# APP_1_DAC_m.net
KiCad netlist of a schematic drawn in Altium Designer
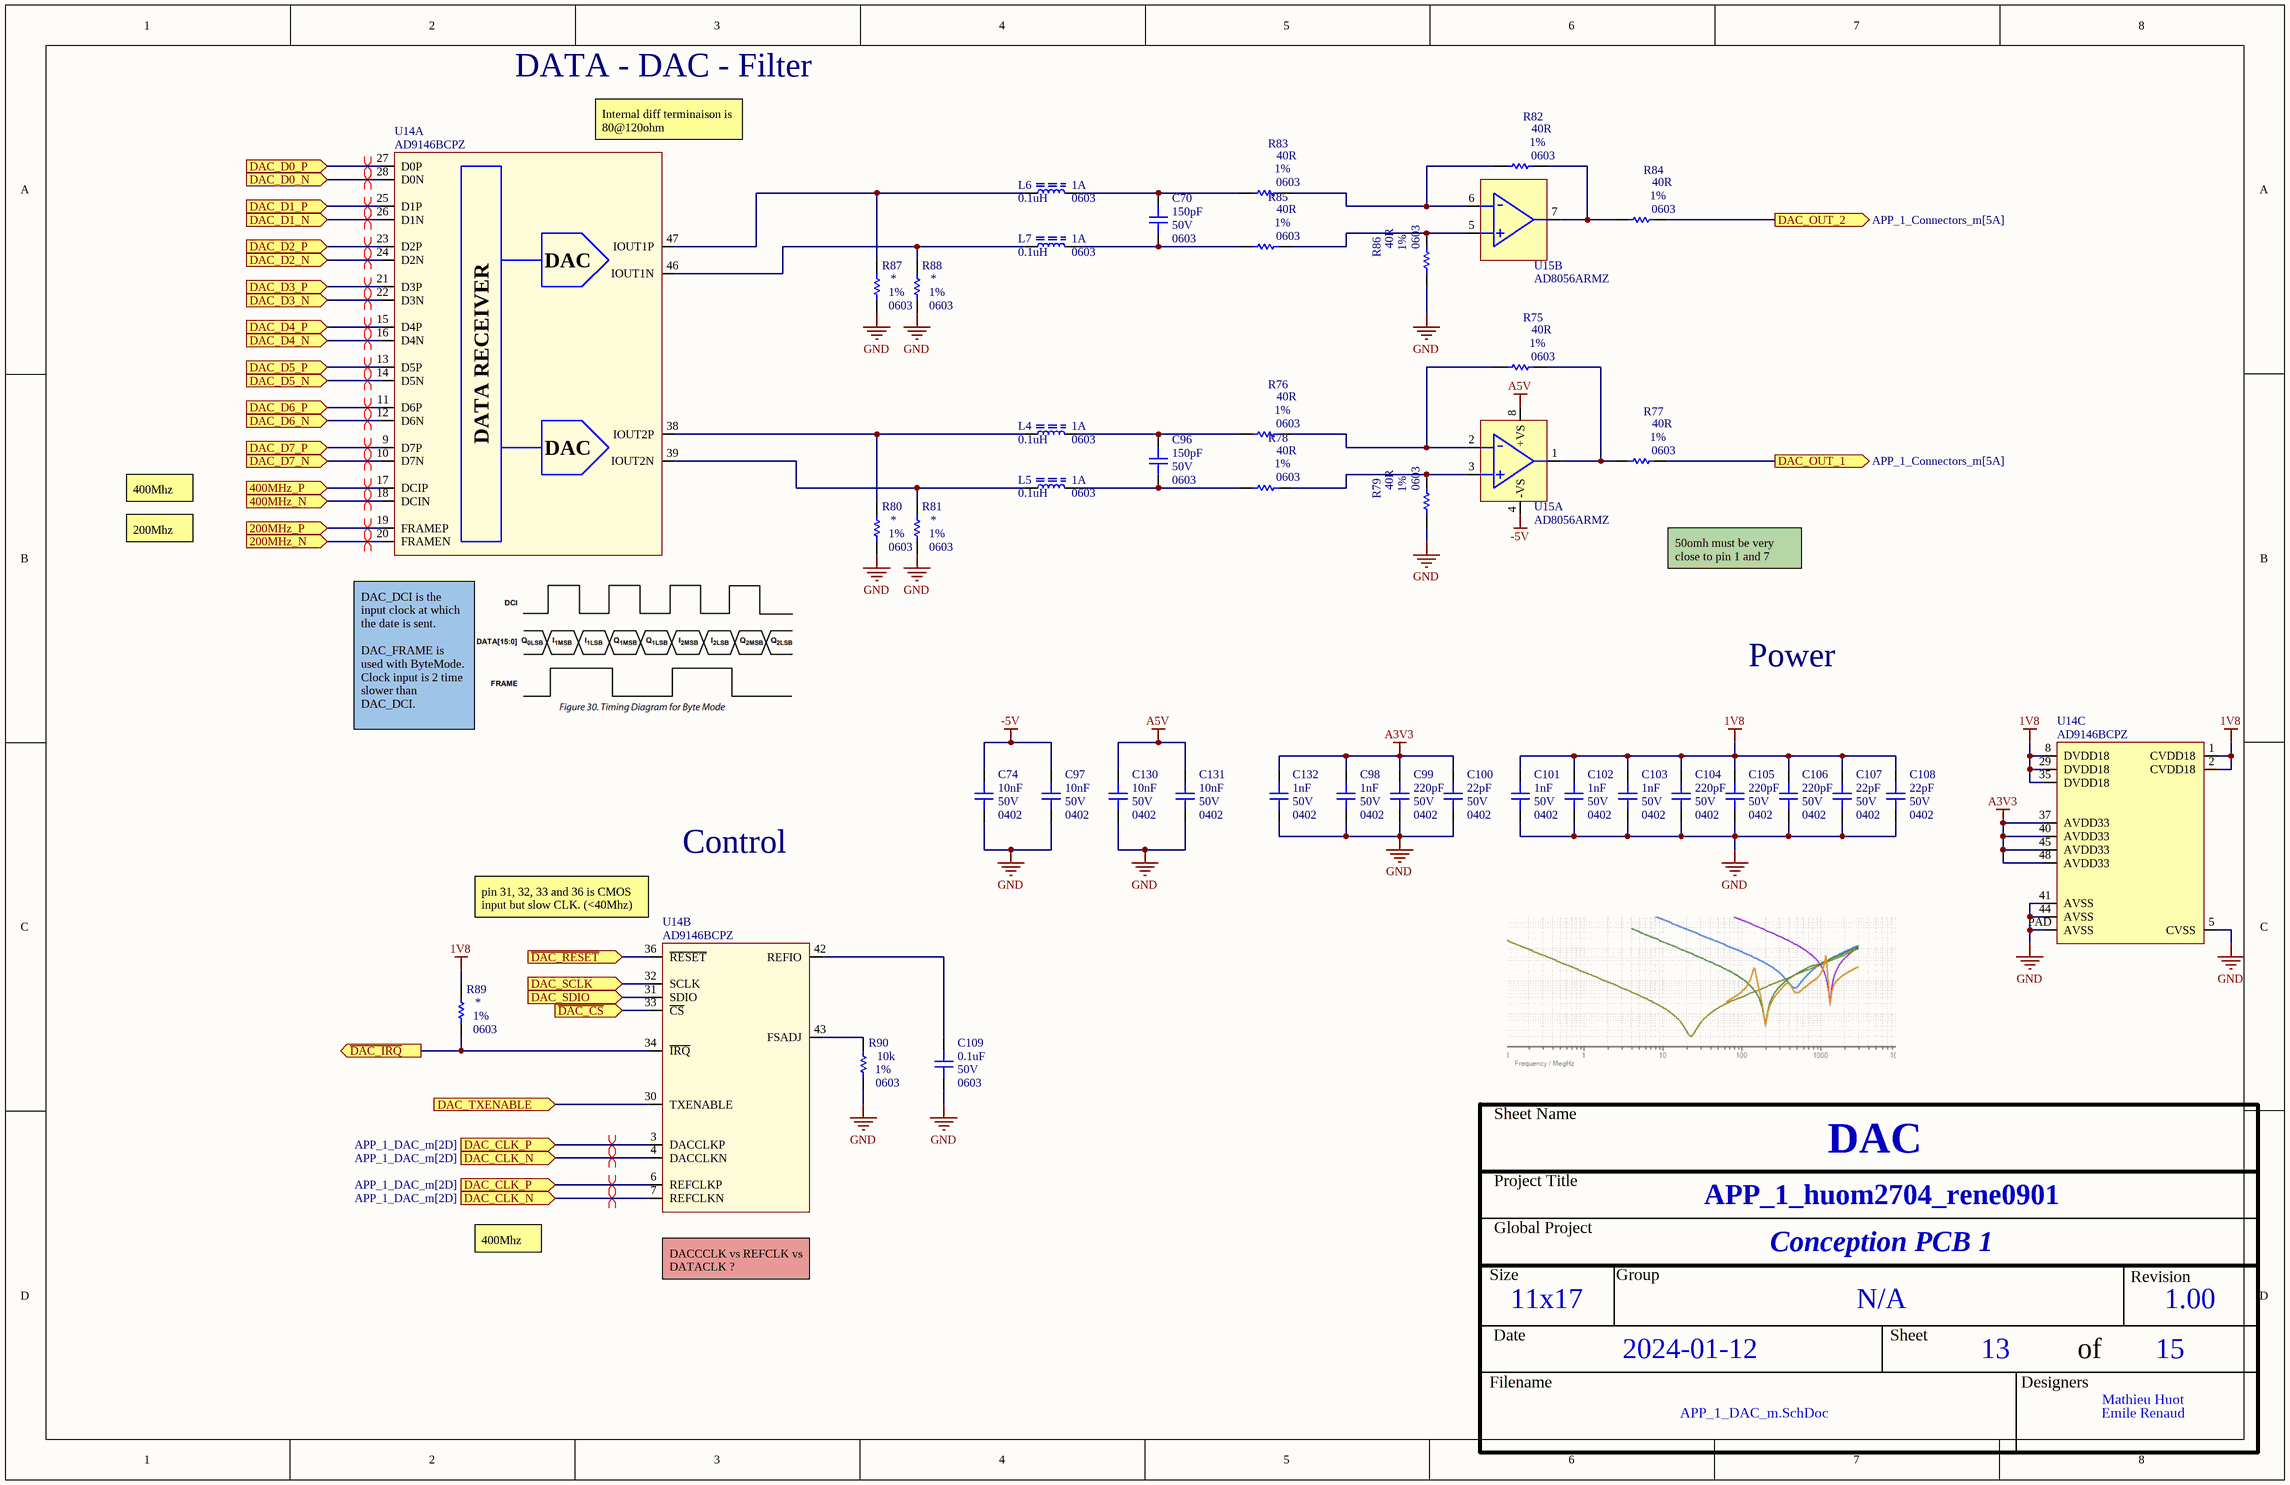
[diagram p0: APP_1_DAC_m.SchDoc]

(export (version "E")
  (design (tool "Eeschema 10.0.6"))
  (components
    (comp (ref "C70")
      (value "150pF")
      (footprint "CAP_0603")
      (description "CAP - 0603")
      (fields
        (field (name "VOLTAGE") "50V")
        (field (name "PACKAGE") "0603")
        (field (name "CREATEDBY") "Jonathan Bouchard")
      )
      (libsource (lib "S7CAS_LIB2023") (part "CAP - 0603"))
    )
    (comp (ref "C74")
      (value "10nF")
      (footprint "CAP_0402")
      (description "CAP - 0402")
      (fields
        (field (name "VOLTAGE") "50V")
        (field (name "PACKAGE") "0402")
        (field (name "CREATEDBY") "Jonathan Bouchard")
      )
      (libsource (lib "S7CAS_LIB2023") (part "CAP - 0402"))
    )
    (comp (ref "C96")
      (value "150pF")
      (footprint "CAP_0603")
      (description "CAP - 0603")
      (fields
        (field (name "VOLTAGE") "50V")
        (field (name "PACKAGE") "0603")
        (field (name "CREATEDBY") "Jonathan Bouchard")
      )
      (libsource (lib "S7CAS_LIB2023") (part "CAP - 0603"))
    )
    (comp (ref "C97")
      (value "10nF")
      (footprint "CAP_0402")
      (description "CAP - 0402")
      (fields
        (field (name "VOLTAGE") "50V")
        (field (name "PACKAGE") "0402")
        (field (name "CREATEDBY") "Jonathan Bouchard")
      )
      (libsource (lib "S7CAS_LIB2023") (part "CAP - 0402"))
    )
    (comp (ref "C98")
      (value "1nF")
      (footprint "CAP_0402")
      (description "CAP - 0402")
      (fields
        (field (name "VOLTAGE") "50V")
        (field (name "PACKAGE") "0402")
        (field (name "CREATEDBY") "Jonathan Bouchard")
      )
      (libsource (lib "S7CAS_LIB2023") (part "CAP - 0402"))
    )
    (comp (ref "C99")
      (value "220pF")
      (footprint "CAP_0402")
      (description "CAP - 0402")
      (fields
        (field (name "VOLTAGE") "50V")
        (field (name "PACKAGE") "0402")
        (field (name "CREATEDBY") "Jonathan Bouchard")
      )
      (libsource (lib "S7CAS_LIB2023") (part "CAP - 0402"))
    )
    (comp (ref "C100")
      (value "22pF")
      (footprint "CAP_0402")
      (description "CAP - 0402")
      (fields
        (field (name "VOLTAGE") "50V")
        (field (name "PACKAGE") "0402")
        (field (name "CREATEDBY") "Jonathan Bouchard")
      )
      (libsource (lib "S7CAS_LIB2023") (part "CAP - 0402"))
    )
    (comp (ref "C101")
      (value "1nF")
      (footprint "CAP_0402")
      (description "CAP - 0402")
      (fields
        (field (name "VOLTAGE") "50V")
        (field (name "PACKAGE") "0402")
        (field (name "CREATEDBY") "Jonathan Bouchard")
      )
      (libsource (lib "S7CAS_LIB2023") (part "CAP - 0402"))
    )
    (comp (ref "C102")
      (value "1nF")
      (footprint "CAP_0402")
      (description "CAP - 0402")
      (fields
        (field (name "VOLTAGE") "50V")
        (field (name "PACKAGE") "0402")
        (field (name "CREATEDBY") "Jonathan Bouchard")
      )
      (libsource (lib "S7CAS_LIB2023") (part "CAP - 0402"))
    )
    (comp (ref "C103")
      (value "1nF")
      (footprint "CAP_0402")
      (description "CAP - 0402")
      (fields
        (field (name "VOLTAGE") "50V")
        (field (name "PACKAGE") "0402")
        (field (name "CREATEDBY") "Jonathan Bouchard")
      )
      (libsource (lib "S7CAS_LIB2023") (part "CAP - 0402"))
    )
    (comp (ref "C104")
      (value "220pF")
      (footprint "CAP_0402")
      (description "CAP - 0402")
      (fields
        (field (name "VOLTAGE") "50V")
        (field (name "PACKAGE") "0402")
        (field (name "CREATEDBY") "Jonathan Bouchard")
      )
      (libsource (lib "S7CAS_LIB2023") (part "CAP - 0402"))
    )
    (comp (ref "C105")
      (value "220pF")
      (footprint "CAP_0402")
      (description "CAP - 0402")
      (fields
        (field (name "VOLTAGE") "50V")
        (field (name "PACKAGE") "0402")
        (field (name "CREATEDBY") "Jonathan Bouchard")
      )
      (libsource (lib "S7CAS_LIB2023") (part "CAP - 0402"))
    )
    (comp (ref "C106")
      (value "220pF")
      (footprint "CAP_0402")
      (description "CAP - 0402")
      (fields
        (field (name "VOLTAGE") "50V")
        (field (name "PACKAGE") "0402")
        (field (name "CREATEDBY") "Jonathan Bouchard")
      )
      (libsource (lib "S7CAS_LIB2023") (part "CAP - 0402"))
    )
    (comp (ref "C107")
      (value "22pF")
      (footprint "CAP_0402")
      (description "CAP - 0402")
      (fields
        (field (name "VOLTAGE") "50V")
        (field (name "PACKAGE") "0402")
        (field (name "CREATEDBY") "Jonathan Bouchard")
      )
      (libsource (lib "S7CAS_LIB2023") (part "CAP - 0402"))
    )
    (comp (ref "C108")
      (value "22pF")
      (footprint "CAP_0402")
      (description "CAP - 0402")
      (fields
        (field (name "VOLTAGE") "50V")
        (field (name "PACKAGE") "0402")
        (field (name "CREATEDBY") "Jonathan Bouchard")
      )
      (libsource (lib "S7CAS_LIB2023") (part "CAP - 0402"))
    )
    (comp (ref "C109")
      (value "0.1uF")
      (footprint "CAP_0603")
      (description "CAP - 0603")
      (fields
        (field (name "VOLTAGE") "50V")
        (field (name "PACKAGE") "0603")
        (field (name "CREATEDBY") "Jonathan Bouchard")
      )
      (libsource (lib "S7CAS_LIB2023") (part "CAP - 0603"))
    )
    (comp (ref "C130")
      (value "10nF")
      (footprint "CAP_0402")
      (description "CAP - 0402")
      (fields
        (field (name "VOLTAGE") "50V")
        (field (name "PACKAGE") "0402")
        (field (name "CREATEDBY") "Jonathan Bouchard")
      )
      (libsource (lib "S7CAS_LIB2023") (part "CAP - 0402"))
    )
    (comp (ref "C131")
      (value "10nF")
      (footprint "CAP_0402")
      (description "CAP - 0402")
      (fields
        (field (name "VOLTAGE") "50V")
        (field (name "PACKAGE") "0402")
        (field (name "CREATEDBY") "Jonathan Bouchard")
      )
      (libsource (lib "S7CAS_LIB2023") (part "CAP - 0402"))
    )
    (comp (ref "C132")
      (value "1nF")
      (footprint "CAP_0402")
      (description "CAP - 0402")
      (fields
        (field (name "VOLTAGE") "50V")
        (field (name "PACKAGE") "0402")
        (field (name "CREATEDBY") "Jonathan Bouchard")
      )
      (libsource (lib "S7CAS_LIB2023") (part "CAP - 0402"))
    )
    (comp (ref "L4")
      (value "0.1uH")
      (footprint "FER_0603")
      (description "FER - 0603")
      (fields
        (field (name "CURRENT") "1A")
        (field (name "PACKAGE") "0603")
        (field (name "CREATEDBY") "Jonathan Bouchard")
      )
      (libsource (lib "S7CAS_LIB2023") (part "FER - 0603"))
    )
    (comp (ref "L5")
      (value "0.1uH")
      (footprint "FER_0603")
      (description "FER - 0603")
      (fields
        (field (name "CURRENT") "1A")
        (field (name "PACKAGE") "0603")
        (field (name "CREATEDBY") "Jonathan Bouchard")
      )
      (libsource (lib "S7CAS_LIB2023") (part "FER - 0603"))
    )
    (comp (ref "L6")
      (value "0.1uH")
      (footprint "FER_0603")
      (description "FER - 0603")
      (fields
        (field (name "CURRENT") "1A")
        (field (name "PACKAGE") "0603")
        (field (name "CREATEDBY") "Jonathan Bouchard")
      )
      (libsource (lib "S7CAS_LIB2023") (part "FER - 0603"))
    )
    (comp (ref "L7")
      (value "0.1uH")
      (footprint "FER_0603")
      (description "FER - 0603")
      (fields
        (field (name "CURRENT") "1A")
        (field (name "PACKAGE") "0603")
        (field (name "CREATEDBY") "Jonathan Bouchard")
      )
      (libsource (lib "S7CAS_LIB2023") (part "FER - 0603"))
    )
    (comp (ref "R75")
      (value "40R")
      (footprint "RES_0603")
      (description "RES - 0603")
      (fields
        (field (name "PACKAGE") "0603")
        (field (name "PRECISION") "1%")
        (field (name "CREATEDBY") "Jonathan Bouchard")
      )
      (libsource (lib "S7CAS_LIB2023") (part "RES - 0603"))
    )
    (comp (ref "R76")
      (value "40R")
      (footprint "RES_0603")
      (description "RES - 0603")
      (fields
        (field (name "PACKAGE") "0603")
        (field (name "PRECISION") "1%")
        (field (name "CREATEDBY") "Jonathan Bouchard")
      )
      (libsource (lib "S7CAS_LIB2023") (part "RES - 0603"))
    )
    (comp (ref "R77")
      (value "40R")
      (footprint "RES_0603")
      (description "RES - 0603")
      (fields
        (field (name "PACKAGE") "0603")
        (field (name "PRECISION") "1%")
        (field (name "CREATEDBY") "Jonathan Bouchard")
      )
      (libsource (lib "S7CAS_LIB2023") (part "RES - 0603"))
    )
    (comp (ref "R78")
      (value "40R")
      (footprint "RES_0603")
      (description "RES - 0603")
      (fields
        (field (name "PACKAGE") "0603")
        (field (name "PRECISION") "1%")
        (field (name "CREATEDBY") "Jonathan Bouchard")
      )
      (libsource (lib "S7CAS_LIB2023") (part "RES - 0603"))
    )
    (comp (ref "R79")
      (value "40R")
      (footprint "RES_0603")
      (description "RES - 0603")
      (fields
        (field (name "PACKAGE") "0603")
        (field (name "PRECISION") "1%")
        (field (name "CREATEDBY") "Jonathan Bouchard")
      )
      (libsource (lib "S7CAS_LIB2023") (part "RES - 0603"))
    )
    (comp (ref "R80")
      (value "RES - 0603")
      (footprint "RES_0603")
      (fields
        (field (name "PACKAGE") "0603")
        (field (name "PRECISION") "1%")
        (field (name "ALTIUM_VALUE") "*")
        (field (name "CREATEDBY") "Jonathan Bouchard")
      )
      (libsource (lib "S7CAS_LIB2023") (part "RES - 0603"))
    )
    (comp (ref "R81")
      (value "RES - 0603")
      (footprint "RES_0603")
      (fields
        (field (name "PACKAGE") "0603")
        (field (name "PRECISION") "1%")
        (field (name "ALTIUM_VALUE") "*")
        (field (name "CREATEDBY") "Jonathan Bouchard")
      )
      (libsource (lib "S7CAS_LIB2023") (part "RES - 0603"))
    )
    (comp (ref "R82")
      (value "40R")
      (footprint "RES_0603")
      (description "RES - 0603")
      (fields
        (field (name "PACKAGE") "0603")
        (field (name "PRECISION") "1%")
        (field (name "CREATEDBY") "Jonathan Bouchard")
      )
      (libsource (lib "S7CAS_LIB2023") (part "RES - 0603"))
    )
    (comp (ref "R83")
      (value "40R")
      (footprint "RES_0603")
      (description "RES - 0603")
      (fields
        (field (name "PACKAGE") "0603")
        (field (name "PRECISION") "1%")
        (field (name "CREATEDBY") "Jonathan Bouchard")
      )
      (libsource (lib "S7CAS_LIB2023") (part "RES - 0603"))
    )
    (comp (ref "R84")
      (value "40R")
      (footprint "RES_0603")
      (description "RES - 0603")
      (fields
        (field (name "PACKAGE") "0603")
        (field (name "PRECISION") "1%")
        (field (name "CREATEDBY") "Jonathan Bouchard")
      )
      (libsource (lib "S7CAS_LIB2023") (part "RES - 0603"))
    )
    (comp (ref "R85")
      (value "40R")
      (footprint "RES_0603")
      (description "RES - 0603")
      (fields
        (field (name "PACKAGE") "0603")
        (field (name "PRECISION") "1%")
        (field (name "CREATEDBY") "Jonathan Bouchard")
      )
      (libsource (lib "S7CAS_LIB2023") (part "RES - 0603"))
    )
    (comp (ref "R86")
      (value "40R")
      (footprint "RES_0603")
      (description "RES - 0603")
      (fields
        (field (name "PACKAGE") "0603")
        (field (name "PRECISION") "1%")
        (field (name "CREATEDBY") "Jonathan Bouchard")
      )
      (libsource (lib "S7CAS_LIB2023") (part "RES - 0603"))
    )
    (comp (ref "R87")
      (value "RES - 0603")
      (footprint "RES_0603")
      (fields
        (field (name "PACKAGE") "0603")
        (field (name "PRECISION") "1%")
        (field (name "ALTIUM_VALUE") "*")
        (field (name "CREATEDBY") "Jonathan Bouchard")
      )
      (libsource (lib "S7CAS_LIB2023") (part "RES - 0603"))
    )
    (comp (ref "R88")
      (value "RES - 0603")
      (footprint "RES_0603")
      (fields
        (field (name "PACKAGE") "0603")
        (field (name "PRECISION") "1%")
        (field (name "ALTIUM_VALUE") "*")
        (field (name "CREATEDBY") "Jonathan Bouchard")
      )
      (libsource (lib "S7CAS_LIB2023") (part "RES - 0603"))
    )
    (comp (ref "R89")
      (value "RES - 0603")
      (footprint "RES_0603")
      (fields
        (field (name "PACKAGE") "0603")
        (field (name "PRECISION") "1%")
        (field (name "ALTIUM_VALUE") "*")
        (field (name "CREATEDBY") "Jonathan Bouchard")
      )
      (libsource (lib "S7CAS_LIB2023") (part "RES - 0603"))
    )
    (comp (ref "R90")
      (value "10k")
      (footprint "RES_0603")
      (description "RES - 0603")
      (fields
        (field (name "PACKAGE") "0603")
        (field (name "PRECISION") "1%")
        (field (name "CREATEDBY") "Jonathan Bouchard")
      )
      (libsource (lib "S7CAS_LIB2023") (part "RES - 0603"))
    )
    (comp (ref "U14")
      (value "AD9146BCPZ")
      (footprint "DAC_AD9146BCPZ")
      (description "DAC - 16BIT SRL HIGH SPEED - QFN-48")
      (fields
        (field (name "VOLTAGE") "3.13 V ~ 3.47 V / 1.71 V ~ 1.89 V")
        (field (name "MFG") "Analog Devices Inc.")
        (field (name "CREATEDBY") "Jonathan Bouchard")
      )
      (libsource (lib "S7CAS_LIB2023") (part "DAC_AD9146BCPZ"))
    )
    (comp (ref "U15")
      (value "AD8056ARMZ")
      (footprint "OPAMP_AD8056ARMZ")
      (description "OPAMP - VFB 300MHZ - 8MSOP")
      (fields
        (field (name "VOLTAGE") "8 V ~ 12 V, ±4 V ~ 6 V")
        (field (name "MFG") "Analog Devices")
        (field (name "CREATEDBY") "Jonathan Bouchard")
      )
      (libsource (lib "S7CAS_LIB2023") (part "OPAMP_AD8056ARMZ"))
    )
  )
  (nets
    (net (code "1") (name "-5V") (class "Default")
      (node (ref "C74") (pin "2") (pinfunction "2_2") (pintype "passive"))
      (node (ref "C97") (pin "2") (pinfunction "2_2") (pintype "passive"))
      (node (ref "U15") (pin "4") (pinfunction "-VS_4") (pintype "passive"))
    )
    (net (code "2") (name "/200MHz_N") (class "Default")
      (node (ref "U14") (pin "20") (pinfunction "FRAMEN_20") (pintype "passive"))
    )
    (net (code "3") (name "/200MHz_P") (class "Default")
      (node (ref "U14") (pin "19") (pinfunction "FRAMEP_19") (pintype "passive"))
    )
    (net (code "4") (name "/400MHz_N") (class "Default")
      (node (ref "U14") (pin "18") (pinfunction "DCIN_18") (pintype "passive"))
    )
    (net (code "5") (name "/400MHz_P") (class "Default")
      (node (ref "U14") (pin "17") (pinfunction "DCIP_17") (pintype "passive"))
    )
    (net (code "6") (name "/DAC_CLK_N") (class "Default")
      (node (ref "U14") (pin "4") (pinfunction "DACCLKN_4") (pintype "passive"))
      (node (ref "U14") (pin "7") (pinfunction "REFCLKN_7") (pintype "passive"))
    )
    (net (code "7") (name "/DAC_CLK_P") (class "Default")
      (node (ref "U14") (pin "3") (pinfunction "DACCLKP_3") (pintype "passive"))
      (node (ref "U14") (pin "6") (pinfunction "REFCLKP_6") (pintype "passive"))
    )
    (net (code "8") (name "/DAC_D0_N") (class "Default")
      (node (ref "U14") (pin "28") (pinfunction "D0N_28") (pintype "passive"))
    )
    (net (code "9") (name "/DAC_D0_P") (class "Default")
      (node (ref "U14") (pin "27") (pinfunction "D0P_27") (pintype "passive"))
    )
    (net (code "10") (name "/DAC_D1_N") (class "Default")
      (node (ref "U14") (pin "26") (pinfunction "D1N_26") (pintype "passive"))
    )
    (net (code "11") (name "/DAC_D1_P") (class "Default")
      (node (ref "U14") (pin "25") (pinfunction "D1P_25") (pintype "passive"))
    )
    (net (code "12") (name "/DAC_D2_N") (class "Default")
      (node (ref "U14") (pin "24") (pinfunction "D2N_24") (pintype "passive"))
    )
    (net (code "13") (name "/DAC_D2_P") (class "Default")
      (node (ref "U14") (pin "23") (pinfunction "D2P_23") (pintype "passive"))
    )
    (net (code "14") (name "/DAC_D3_N") (class "Default")
      (node (ref "U14") (pin "22") (pinfunction "D3N_22") (pintype "passive"))
    )
    (net (code "15") (name "/DAC_D3_P") (class "Default")
      (node (ref "U14") (pin "21") (pinfunction "D3P_21") (pintype "passive"))
    )
    (net (code "16") (name "/DAC_D4_N") (class "Default")
      (node (ref "U14") (pin "16") (pinfunction "D4N_16") (pintype "passive"))
    )
    (net (code "17") (name "/DAC_D4_P") (class "Default")
      (node (ref "U14") (pin "15") (pinfunction "D4P_15") (pintype "passive"))
    )
    (net (code "18") (name "/DAC_D5_N") (class "Default")
      (node (ref "U14") (pin "14") (pinfunction "D5N_14") (pintype "passive"))
    )
    (net (code "19") (name "/DAC_D5_P") (class "Default")
      (node (ref "U14") (pin "13") (pinfunction "D5P_13") (pintype "passive"))
    )
    (net (code "20") (name "/DAC_D6_N") (class "Default")
      (node (ref "U14") (pin "12") (pinfunction "D6N_12") (pintype "passive"))
    )
    (net (code "21") (name "/DAC_D6_P") (class "Default")
      (node (ref "U14") (pin "11") (pinfunction "D6P_11") (pintype "passive"))
    )
    (net (code "22") (name "/DAC_D7_N") (class "Default")
      (node (ref "U14") (pin "10") (pinfunction "D7N_10") (pintype "passive"))
    )
    (net (code "23") (name "/DAC_D7_P") (class "Default")
      (node (ref "U14") (pin "9") (pinfunction "D7P_9") (pintype "passive"))
    )
    (net (code "24") (name "/DAC_OUT_1") (class "Default")
      (node (ref "R77") (pin "1") (pinfunction "1_1") (pintype "passive"))
    )
    (net (code "25") (name "/DAC_OUT_2") (class "Default")
      (node (ref "R84") (pin "1") (pinfunction "1_1") (pintype "passive"))
    )
    (net (code "26") (name "/DAC_SCLK") (class "Default")
      (node (ref "U14") (pin "32") (pinfunction "SCLK_32") (pintype "passive"))
    )
    (net (code "27") (name "/DAC_SDIO") (class "Default")
      (node (ref "U14") (pin "31") (pinfunction "SDIO_31") (pintype "passive"))
    )
    (net (code "28") (name "/DAC_TXENABLE") (class "Default")
      (node (ref "U14") (pin "30") (pinfunction "TXENABLE_30") (pintype "passive"))
    )
    (net (code "29") (name "/~{DAC_CS}") (class "Default")
      (node (ref "U14") (pin "33") (pinfunction "~{CS}_33") (pintype "passive"))
    )
    (net (code "30") (name "/~{DAC_IRQ}") (class "Default")
      (node (ref "R89") (pin "1") (pinfunction "1_1") (pintype "passive"))
      (node (ref "U14") (pin "34") (pinfunction "~{IRQ}_34") (pintype "passive"))
    )
    (net (code "31") (name "/~{DAC_RESET}") (class "Default")
      (node (ref "U14") (pin "36") (pinfunction "~{RESET}_36") (pintype "passive"))
    )
    (net (code "32") (name "1V8") (class "Default")
      (node (ref "C101") (pin "2") (pinfunction "2_2") (pintype "passive"))
      (node (ref "C102") (pin "2") (pinfunction "2_2") (pintype "passive"))
      (node (ref "C103") (pin "2") (pinfunction "2_2") (pintype "passive"))
      (node (ref "C104") (pin "2") (pinfunction "2_2") (pintype "passive"))
      (node (ref "C105") (pin "2") (pinfunction "2_2") (pintype "passive"))
      (node (ref "C106") (pin "2") (pinfunction "2_2") (pintype "passive"))
      (node (ref "C107") (pin "2") (pinfunction "2_2") (pintype "passive"))
      (node (ref "C108") (pin "2") (pinfunction "2_2") (pintype "passive"))
      (node (ref "R89") (pin "2") (pinfunction "2_2") (pintype "passive"))
      (node (ref "U14") (pin "1") (pinfunction "CVDD18_1") (pintype "passive"))
      (node (ref "U14") (pin "2") (pinfunction "CVDD18_2") (pintype "passive"))
      (node (ref "U14") (pin "29") (pinfunction "DVDD18_29") (pintype "passive"))
      (node (ref "U14") (pin "35") (pinfunction "DVDD18_35") (pintype "passive"))
      (node (ref "U14") (pin "8") (pinfunction "DVDD18_8") (pintype "passive"))
    )
    (net (code "33") (name "A3V3") (class "Default")
      (node (ref "C100") (pin "2") (pinfunction "2_2") (pintype "passive"))
      (node (ref "C132") (pin "2") (pinfunction "2_2") (pintype "passive"))
      (node (ref "C98") (pin "2") (pinfunction "2_2") (pintype "passive"))
      (node (ref "C99") (pin "2") (pinfunction "2_2") (pintype "passive"))
      (node (ref "U14") (pin "37") (pinfunction "AVDD33_37") (pintype "passive"))
      (node (ref "U14") (pin "40") (pinfunction "AVDD33_40") (pintype "passive"))
      (node (ref "U14") (pin "45") (pinfunction "AVDD33_45") (pintype "passive"))
      (node (ref "U14") (pin "48") (pinfunction "AVDD33_48") (pintype "passive"))
    )
    (net (code "34") (name "A5V") (class "Default")
      (node (ref "C130") (pin "2") (pinfunction "2_2") (pintype "passive"))
      (node (ref "C131") (pin "2") (pinfunction "2_2") (pintype "passive"))
      (node (ref "U15") (pin "8") (pinfunction "+VS_8") (pintype "passive"))
    )
    (net (code "35") (name "GND") (class "Default")
      (node (ref "C100") (pin "1") (pinfunction "1_1") (pintype "passive"))
      (node (ref "C101") (pin "1") (pinfunction "1_1") (pintype "passive"))
      (node (ref "C102") (pin "1") (pinfunction "1_1") (pintype "passive"))
      (node (ref "C103") (pin "1") (pinfunction "1_1") (pintype "passive"))
      (node (ref "C104") (pin "1") (pinfunction "1_1") (pintype "passive"))
      (node (ref "C105") (pin "1") (pinfunction "1_1") (pintype "passive"))
      (node (ref "C106") (pin "1") (pinfunction "1_1") (pintype "passive"))
      (node (ref "C107") (pin "1") (pinfunction "1_1") (pintype "passive"))
      (node (ref "C108") (pin "1") (pinfunction "1_1") (pintype "passive"))
      (node (ref "C109") (pin "1") (pinfunction "1_1") (pintype "passive"))
      (node (ref "C130") (pin "1") (pinfunction "1_1") (pintype "passive"))
      (node (ref "C131") (pin "1") (pinfunction "1_1") (pintype "passive"))
      (node (ref "C132") (pin "1") (pinfunction "1_1") (pintype "passive"))
      (node (ref "C74") (pin "1") (pinfunction "1_1") (pintype "passive"))
      (node (ref "C97") (pin "1") (pinfunction "1_1") (pintype "passive"))
      (node (ref "C98") (pin "1") (pinfunction "1_1") (pintype "passive"))
      (node (ref "C99") (pin "1") (pinfunction "1_1") (pintype "passive"))
      (node (ref "R79") (pin "2") (pinfunction "2_2") (pintype "passive"))
      (node (ref "R80") (pin "1") (pinfunction "1_1") (pintype "passive"))
      (node (ref "R81") (pin "1") (pinfunction "1_1") (pintype "passive"))
      (node (ref "R86") (pin "2") (pinfunction "2_2") (pintype "passive"))
      (node (ref "R87") (pin "1") (pinfunction "1_1") (pintype "passive"))
      (node (ref "R88") (pin "1") (pinfunction "1_1") (pintype "passive"))
      (node (ref "R90") (pin "1") (pinfunction "1_1") (pintype "passive"))
      (node (ref "U14") (pin "41") (pinfunction "AVSS_41") (pintype "passive"))
      (node (ref "U14") (pin "44") (pinfunction "AVSS_44") (pintype "passive"))
      (node (ref "U14") (pin "5") (pinfunction "CVSS_5") (pintype "passive"))
      (node (ref "U14") (pin "PAD") (pinfunction "AVSS_PAD") (pintype "passive"))
    )
    (net (code "36") (name "Net-(C70-Pad1)") (class "Default")
      (node (ref "C70") (pin "1") (pinfunction "1_1") (pintype "passive"))
      (node (ref "L7") (pin "1") (pinfunction "1_1") (pintype "passive"))
      (node (ref "R85") (pin "2") (pinfunction "2_2") (pintype "passive"))
    )
    (net (code "37") (name "Net-(C70-Pad2)") (class "Default")
      (node (ref "C70") (pin "2") (pinfunction "2_2") (pintype "passive"))
      (node (ref "L6") (pin "1") (pinfunction "1_1") (pintype "passive"))
      (node (ref "R83") (pin "2") (pinfunction "2_2") (pintype "passive"))
    )
    (net (code "38") (name "Net-(C96-Pad1)") (class "Default")
      (node (ref "C96") (pin "1") (pinfunction "1_1") (pintype "passive"))
      (node (ref "L5") (pin "1") (pinfunction "1_1") (pintype "passive"))
      (node (ref "R78") (pin "2") (pinfunction "2_2") (pintype "passive"))
    )
    (net (code "39") (name "Net-(C96-Pad2)") (class "Default")
      (node (ref "C96") (pin "2") (pinfunction "2_2") (pintype "passive"))
      (node (ref "L4") (pin "1") (pinfunction "1_1") (pintype "passive"))
      (node (ref "R76") (pin "2") (pinfunction "2_2") (pintype "passive"))
    )
    (net (code "40") (name "Net-(U14A-IOUT1N)") (class "Default")
      (node (ref "L7") (pin "2") (pinfunction "2_2") (pintype "passive"))
      (node (ref "R88") (pin "2") (pinfunction "2_2") (pintype "passive"))
      (node (ref "U14") (pin "46") (pinfunction "IOUT1N_46") (pintype "passive"))
    )
    (net (code "41") (name "Net-(U14A-IOUT1P)") (class "Default")
      (node (ref "L6") (pin "2") (pinfunction "2_2") (pintype "passive"))
      (node (ref "R87") (pin "2") (pinfunction "2_2") (pintype "passive"))
      (node (ref "U14") (pin "47") (pinfunction "IOUT1P_47") (pintype "passive"))
    )
    (net (code "42") (name "Net-(U14A-IOUT2N)") (class "Default")
      (node (ref "L5") (pin "2") (pinfunction "2_2") (pintype "passive"))
      (node (ref "R81") (pin "2") (pinfunction "2_2") (pintype "passive"))
      (node (ref "U14") (pin "39") (pinfunction "IOUT2N_39") (pintype "passive"))
    )
    (net (code "43") (name "Net-(U14A-IOUT2P)") (class "Default")
      (node (ref "L4") (pin "2") (pinfunction "2_2") (pintype "passive"))
      (node (ref "R80") (pin "2") (pinfunction "2_2") (pintype "passive"))
      (node (ref "U14") (pin "38") (pinfunction "IOUT2P_38") (pintype "passive"))
    )
    (net (code "44") (name "Net-(U14B-FSADJ)") (class "Default")
      (node (ref "R90") (pin "2") (pinfunction "2_2") (pintype "passive"))
      (node (ref "U14") (pin "43") (pinfunction "FSADJ_43") (pintype "passive"))
    )
    (net (code "45") (name "Net-(U14B-REFIO)") (class "Default")
      (node (ref "C109") (pin "2") (pinfunction "2_2") (pintype "passive"))
      (node (ref "U14") (pin "42") (pinfunction "REFIO_42") (pintype "passive"))
    )
    (net (code "46") (name "Net-(U15A-+IN1)") (class "Default")
      (node (ref "R78") (pin "1") (pinfunction "1_1") (pintype "passive"))
      (node (ref "R79") (pin "1") (pinfunction "1_1") (pintype "passive"))
      (node (ref "U15") (pin "3") (pinfunction "+IN1_3") (pintype "passive"))
    )
    (net (code "47") (name "Net-(U15A--IN1)") (class "Default")
      (node (ref "R75") (pin "2") (pinfunction "2_2") (pintype "passive"))
      (node (ref "R76") (pin "1") (pinfunction "1_1") (pintype "passive"))
      (node (ref "U15") (pin "2") (pinfunction "-IN1_2") (pintype "passive"))
    )
    (net (code "48") (name "Net-(U15A-OUT1)") (class "Default")
      (node (ref "R75") (pin "1") (pinfunction "1_1") (pintype "passive"))
      (node (ref "R77") (pin "2") (pinfunction "2_2") (pintype "passive"))
      (node (ref "U15") (pin "1") (pinfunction "OUT1_1") (pintype "passive"))
    )
    (net (code "49") (name "Net-(U15B-+IN2)") (class "Default")
      (node (ref "R85") (pin "1") (pinfunction "1_1") (pintype "passive"))
      (node (ref "R86") (pin "1") (pinfunction "1_1") (pintype "passive"))
      (node (ref "U15") (pin "5") (pinfunction "+IN2_5") (pintype "passive"))
    )
    (net (code "50") (name "Net-(U15B--IN2)") (class "Default")
      (node (ref "R82") (pin "2") (pinfunction "2_2") (pintype "passive"))
      (node (ref "R83") (pin "1") (pinfunction "1_1") (pintype "passive"))
      (node (ref "U15") (pin "6") (pinfunction "-IN2_6") (pintype "passive"))
    )
    (net (code "51") (name "Net-(U15B-OUT2)") (class "Default")
      (node (ref "R82") (pin "1") (pinfunction "1_1") (pintype "passive"))
      (node (ref "R84") (pin "2") (pinfunction "2_2") (pintype "passive"))
      (node (ref "U15") (pin "7") (pinfunction "OUT2_7") (pintype "passive"))
    )
  )
)
